# 09_-_Controlled_Power.net
KiCad netlist of a schematic drawn in Altium Designer
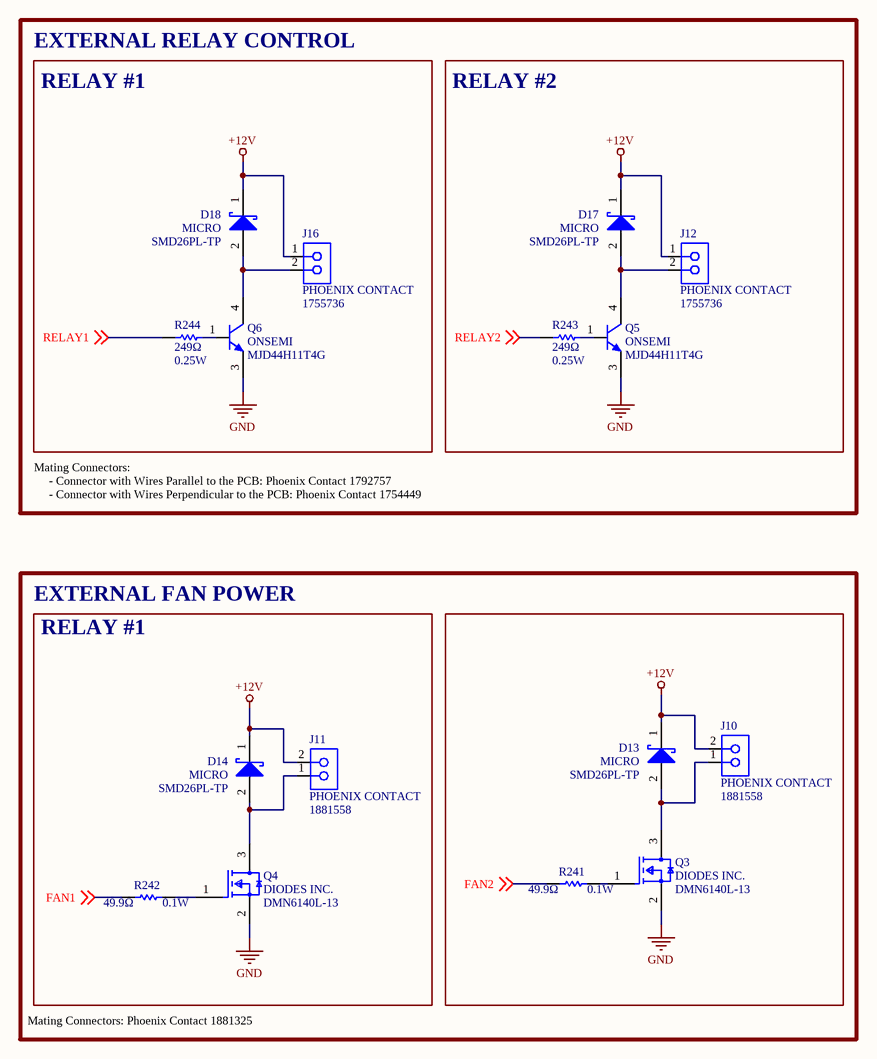
[diagram p0: 09 - Controlled Power.SchDoc]

(export (version "E")
  (design (tool "Eeschema 10.0.6"))
  (components
    (comp (ref "D13")
      (value "SMD26PL-TP")
      (footprint "ONSC-SOD-123FL-2-498-01_V")
      (description "DIODE SCHOTTKY 60V 2A SOD123FL")
      (fields (field (name "MANUFACTURER") "MICRO"))
      (libsource (lib "CRD25DA12N-FMC") (part "SMD26PL-TP"))
    )
    (comp (ref "D14")
      (value "SMD26PL-TP")
      (footprint "ONSC-SOD-123FL-2-498-01_V")
      (description "DIODE SCHOTTKY 60V 2A SOD123FL")
      (fields (field (name "MANUFACTURER") "MICRO"))
      (libsource (lib "CRD25DA12N-FMC") (part "SMD26PL-TP"))
    )
    (comp (ref "D17")
      (value "SMD26PL-TP")
      (footprint "ONSC-SOD-123FL-2-498-01_V")
      (description "DIODE SCHOTTKY 60V 2A SOD123FL")
      (fields (field (name "MANUFACTURER") "MICRO"))
      (libsource (lib "CRD25DA12N-FMC") (part "SMD26PL-TP"))
    )
    (comp (ref "D18")
      (value "SMD26PL-TP")
      (footprint "ONSC-SOD-123FL-2-498-01_V")
      (description "DIODE SCHOTTKY 60V 2A SOD123FL")
      (fields (field (name "MANUFACTURER") "MICRO"))
      (libsource (lib "CRD25DA12N-FMC") (part "SMD26PL-TP"))
    )
    (comp (ref "J10")
      (value "1881558")
      (footprint "CONN_1881558")
      (description "TERM BLOCK HDR 2POS VERT 2.5MM")
      (fields
        (field (name "MANUFACTURER") "PHOENIX CONTACT")
        (field (name "MANUFACTURER PART NUMBER") "1881558")
      )
      (libsource (lib "CRD25DA12N-FMC") (part "1881558"))
    )
    (comp (ref "J11")
      (value "1881558")
      (footprint "CONN_1881558")
      (description "TERM BLOCK HDR 2POS VERT 2.5MM")
      (fields
        (field (name "MANUFACTURER") "PHOENIX CONTACT")
        (field (name "MANUFACTURER PART NUMBER") "1881558")
      )
      (libsource (lib "CRD25DA12N-FMC") (part "1881558"))
    )
    (comp (ref "J12")
      (value "1755736")
      (footprint "1755736")
      (description "TERM BLOCK HDR 2POS VERT 5.08MM")
      (fields
        (field (name "MANUFACTURER") "PHOENIX CONTACT")
        (field (name "MANUFACTURER PART NUMBER") "1755736")
      )
      (libsource (lib "Inverter_25kW") (part "1755736"))
    )
    (comp (ref "J16")
      (value "1755736")
      (footprint "1755736")
      (description "TERM BLOCK HDR 2POS VERT 5.08MM")
      (fields
        (field (name "MANUFACTURER") "PHOENIX CONTACT")
        (field (name "MANUFACTURER PART NUMBER") "1755736")
      )
      (libsource (lib "Inverter_25kW") (part "1755736"))
    )
    (comp (ref "Q3")
      (value "DMN6140L-13")
      (footprint "FP-SOT23-MFG")
      (description "MOSFET N-CH 60V 1.6A SOT23")
      (fields
        (field (name "OCTOPART") "https://octopart.com/dmn6140l-13-diodes+inc.-38898616")
        (field (name "MANUFACTURER") "DIODES INC.")
      )
      (libsource (lib "Altium Content Vault") (part "0a9ea7c96deaaede766a5b531c28de0"))
    )
    (comp (ref "Q4")
      (value "DMN6140L-13")
      (footprint "FP-SOT23-MFG")
      (description "MOSFET N-CH 60V 1.6A SOT23")
      (fields
        (field (name "OCTOPART") "https://octopart.com/dmn6140l-13-diodes+inc.-38898616")
        (field (name "MANUFACTURER") "DIODES INC.")
      )
      (libsource (lib "Altium Content Vault") (part "0a9ea7c96deaaede766a5b531c28de0"))
    )
    (comp (ref "Q5")
      (value "MJD44H11T4G")
      (footprint "ONSC-DPAK-3-369C-01_V")
      (description "TRANS NPN 80V 8A DPAK")
      (fields (field (name "MANUFACTURER") "ONSEMI") (field (name "MANUFACTURER PART NUMBER") "MJD44H11T4G"))
      (libsource (lib "Altium Content Vault") (part "ONSC-NPN-B1E3C4-3"))
    )
    (comp (ref "Q6")
      (value "MJD44H11T4G")
      (footprint "ONSC-DPAK-3-369C-01_V")
      (description "TRANS NPN 80V 8A DPAK")
      (fields (field (name "MANUFACTURER") "ONSEMI") (field (name "MANUFACTURER PART NUMBER") "MJD44H11T4G"))
      (libsource (lib "Altium Content Vault") (part "ONSC-NPN-B1E3C4-3"))
    )
    (comp (ref "R241")
      (value "ERJ-3EKF49R9V")
      (footprint "FP-MCR03-IPC_B")
      (description "RES SMD 49.9 OHM 1% 1/10W 0603")
      (fields
        (field (name "MANUFACTURER") "PANASONIC")
        (field (name "TOLERANCE") "1%")
        (field (name "RESISTANCE") "49.9Ω")
        (field (name "POWER RATING") "0.1W")
      )
      (libsource (lib "Inverter_25kW") (part "ERJ-3EKF49R9V"))
    )
    (comp (ref "R242")
      (value "ERJ-3EKF49R9V")
      (footprint "FP-MCR03-IPC_B")
      (description "RES SMD 49.9 OHM 1% 1/10W 0603")
      (fields
        (field (name "MANUFACTURER") "PANASONIC")
        (field (name "TOLERANCE") "1%")
        (field (name "RESISTANCE") "49.9Ω")
        (field (name "POWER RATING") "0.1W")
      )
      (libsource (lib "Inverter_25kW") (part "ERJ-3EKF49R9V"))
    )
    (comp (ref "R243")
      (value "RC1206FR-07249RL")
      (footprint "FP-MCR18-IPC_A")
      (description "RES 249 OHM 1% 1/4W 1206")
      (fields
        (field (name "MANUFACTURER") "YAGEO")
        (field (name "TOLERANCE") "1%")
        (field (name "RESISTANCE") "249Ω")
        (field (name "POWER RATING") "0.25W")
      )
      (libsource (lib "Inverter_25kW") (part "RC1206FR-07249RL"))
    )
    (comp (ref "R244")
      (value "RC1206FR-07249RL")
      (footprint "FP-MCR18-IPC_A")
      (description "RES 249 OHM 1% 1/4W 1206")
      (fields
        (field (name "MANUFACTURER") "YAGEO")
        (field (name "TOLERANCE") "1%")
        (field (name "RESISTANCE") "249Ω")
        (field (name "POWER RATING") "0.25W")
      )
      (libsource (lib "Inverter_25kW") (part "RC1206FR-07249RL"))
    )
  )
  (nets
    (net (code "1") (name "+12V") (class "Default")
      (node (ref "D13") (pin "1") (pinfunction "K_1") (pintype "passive"))
      (node (ref "D14") (pin "1") (pinfunction "K_1") (pintype "passive"))
      (node (ref "D17") (pin "1") (pinfunction "K_1") (pintype "passive"))
      (node (ref "D18") (pin "1") (pinfunction "K_1") (pintype "passive"))
      (node (ref "J10") (pin "2") (pinfunction "2_2") (pintype "passive"))
      (node (ref "J11") (pin "2") (pinfunction "2_2") (pintype "passive"))
      (node (ref "J12") (pin "1") (pinfunction "1_1") (pintype "passive"))
      (node (ref "J16") (pin "1") (pinfunction "1_1") (pintype "passive"))
    )
    (net (code "2") (name "FAN1") (class "Default")
      (node (ref "R242") (pin "1") (pinfunction "1_1") (pintype "passive"))
    )
    (net (code "3") (name "FAN2") (class "Default")
      (node (ref "R241") (pin "1") (pinfunction "1_1") (pintype "passive"))
    )
    (net (code "4") (name "GND") (class "Default")
      (node (ref "Q3") (pin "2") (pinfunction "S_2") (pintype "passive"))
      (node (ref "Q4") (pin "2") (pinfunction "S_2") (pintype "passive"))
      (node (ref "Q5") (pin "3") (pinfunction "E_3") (pintype "passive"))
      (node (ref "Q6") (pin "3") (pinfunction "E_3") (pintype "passive"))
    )
    (net (code "5") (name "Net-(D13-A)") (class "Default")
      (node (ref "D13") (pin "2") (pinfunction "A_2") (pintype "passive"))
      (node (ref "J10") (pin "1") (pinfunction "1_1") (pintype "passive"))
      (node (ref "Q3") (pin "3") (pinfunction "D_3") (pintype "passive"))
    )
    (net (code "6") (name "Net-(D14-A)") (class "Default")
      (node (ref "D14") (pin "2") (pinfunction "A_2") (pintype "passive"))
      (node (ref "J11") (pin "1") (pinfunction "1_1") (pintype "passive"))
      (node (ref "Q4") (pin "3") (pinfunction "D_3") (pintype "passive"))
    )
    (net (code "7") (name "Net-(D17-A)") (class "Default")
      (node (ref "D17") (pin "2") (pinfunction "A_2") (pintype "passive"))
      (node (ref "J12") (pin "2") (pinfunction "2_2") (pintype "passive"))
      (node (ref "Q5") (pin "4") (pinfunction "C_4") (pintype "passive"))
    )
    (net (code "8") (name "Net-(D18-A)") (class "Default")
      (node (ref "D18") (pin "2") (pinfunction "A_2") (pintype "passive"))
      (node (ref "J16") (pin "2") (pinfunction "2_2") (pintype "passive"))
      (node (ref "Q6") (pin "4") (pinfunction "C_4") (pintype "passive"))
    )
    (net (code "9") (name "Net-(Q3-G)") (class "Default")
      (node (ref "Q3") (pin "1") (pinfunction "G_1") (pintype "passive"))
      (node (ref "R241") (pin "2") (pinfunction "2_2") (pintype "passive"))
    )
    (net (code "10") (name "Net-(Q4-G)") (class "Default")
      (node (ref "Q4") (pin "1") (pinfunction "G_1") (pintype "passive"))
      (node (ref "R242") (pin "2") (pinfunction "2_2") (pintype "passive"))
    )
    (net (code "11") (name "Net-(Q5-B)") (class "Default")
      (node (ref "Q5") (pin "1") (pinfunction "B_1") (pintype "passive"))
      (node (ref "R243") (pin "2") (pinfunction "2_2") (pintype "passive"))
    )
    (net (code "12") (name "Net-(Q6-B)") (class "Default")
      (node (ref "Q6") (pin "1") (pinfunction "B_1") (pintype "passive"))
      (node (ref "R244") (pin "2") (pinfunction "2_2") (pintype "passive"))
    )
    (net (code "13") (name "RELAY1") (class "Default")
      (node (ref "R244") (pin "1") (pinfunction "1_1") (pintype "passive"))
    )
    (net (code "14") (name "RELAY2") (class "Default")
      (node (ref "R243") (pin "1") (pinfunction "1_1") (pintype "passive"))
    )
  )
)
